# MCU.net
KiCad netlist of a schematic drawn in Altium Designer
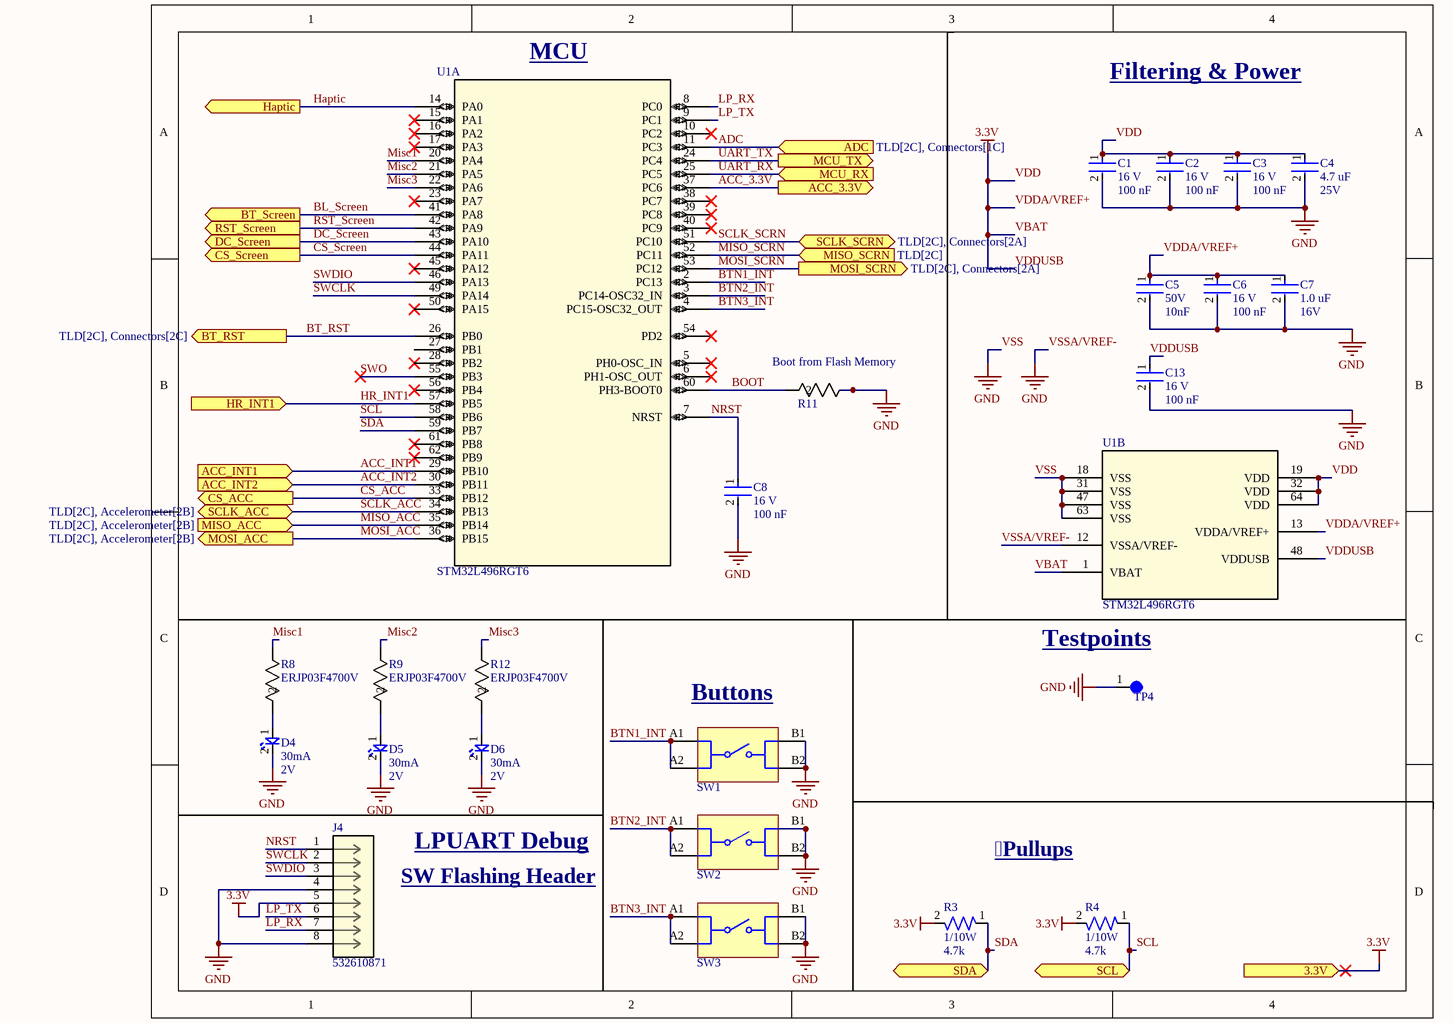
[diagram p0: MCU.SchDoc]

(export (version "E")
  (design (tool "Eeschema 10.0.6"))
  (components
    (comp (ref "C1")
      (value "CC0402KRX7R7BB104")
      (footprint "CAP-0402")
      (description "CAP CER 0.1UF 16V X7R 0402")
      (fields (field (name "VOLTAGE RATING") "16 V") (field (name "CAPACITANCE") "100 nF"))
      (libsource (lib "JLC_25") (part "CAP-0.1U-0001"))
    )
    (comp (ref "C2")
      (value "CC0402KRX7R7BB104")
      (footprint "CAP-0402")
      (description "CAP CER 0.1UF 16V X7R 0402")
      (fields (field (name "VOLTAGE RATING") "16 V") (field (name "CAPACITANCE") "100 nF"))
      (libsource (lib "JLC_25") (part "CAP-0.1U-0001"))
    )
    (comp (ref "C3")
      (value "CC0402KRX7R7BB104")
      (footprint "CAP-0402")
      (description "CAP CER 0.1UF 16V X7R 0402")
      (fields (field (name "VOLTAGE RATING") "16 V") (field (name "CAPACITANCE") "100 nF"))
      (libsource (lib "JLC_25") (part "CAP-0.1U-0001"))
    )
    (comp (ref "C4")
      (value "CC0603KRX5R8BB475")
      (footprint "CAP-0603")
      (description "CAP CER 4.7UF 25V X5R 0603")
      (fields (field (name "CAPACITANCE") "4.7 uF") (field (name "VOLTAGE") "25V"))
      (libsource (lib "JLC_25") (part "CAP-4.7U-0001"))
    )
    (comp (ref "C5")
      (value "GRM2195C1H103JA01D")
      (footprint "CAP-0805")
      (description "CAP CER 10000PF 50V C0G/NP0 0805")
      (fields (field (name "VOLTAGE") "50V") (field (name "CAPACITANCE") "10nF"))
      (libsource (lib "JLC_25") (part "CAP-10N-0001"))
    )
    (comp (ref "C6")
      (value "CC0402KRX7R7BB104")
      (footprint "CAP-0402")
      (description "CAP CER 0.1UF 16V X7R 0402")
      (fields (field (name "VOLTAGE RATING") "16 V") (field (name "CAPACITANCE") "100 nF"))
      (libsource (lib "JLC_25") (part "CAP-0.1U-0001"))
    )
    (comp (ref "C7")
      (value "CC0603KRX7R7BB105")
      (footprint "CAP-0603")
      (description "CAP CER 1UF 16V X7R 0603")
      (fields (field (name "CAPACITANCE") "1.0 uF") (field (name "VOLTAGE") "16V"))
      (libsource (lib "JLC_25") (part "CAP-1U-0002"))
    )
    (comp (ref "C8")
      (value "CC0402KRX7R7BB104")
      (footprint "CAP-0402")
      (description "CAP CER 0.1UF 16V X7R 0402")
      (fields (field (name "VOLTAGE RATING") "16 V") (field (name "CAPACITANCE") "100 nF"))
      (libsource (lib "JLC_25") (part "CAP-0.1U-0001"))
    )
    (comp (ref "C13")
      (value "CC0402KRX7R7BB104")
      (footprint "CAP-0402")
      (description "CAP CER 0.1UF 16V X7R 0402")
      (fields (field (name "VOLTAGE RATING") "16 V") (field (name "CAPACITANCE") "100 nF"))
      (libsource (lib "JLC_25") (part "CAP-0.1U-0001"))
    )
    (comp (ref "D4")
      (value "BL-HKC36G-AV-TRB")
      (footprint "LED-0603")
      (description "LED YELLOW CLEAR 0603 SMD")
      (fields (field (name "FORWARD CURRENT") "30mA") (field (name "FORWARD VOLTAGE") "2V"))
      (libsource (lib "JLC_25") (part "LED-0001"))
    )
    (comp (ref "D5")
      (value "BL-HKC36G-AV-TRB")
      (footprint "LED-0603")
      (description "LED YELLOW CLEAR 0603 SMD")
      (fields (field (name "FORWARD CURRENT") "30mA") (field (name "FORWARD VOLTAGE") "2V"))
      (libsource (lib "JLC_25") (part "LED-0001"))
    )
    (comp (ref "D6")
      (value "BL-HKC36G-AV-TRB")
      (footprint "LED-0603")
      (description "LED YELLOW CLEAR 0603 SMD")
      (fields (field (name "FORWARD CURRENT") "30mA") (field (name "FORWARD VOLTAGE") "2V"))
      (libsource (lib "JLC_25") (part "LED-0001"))
    )
    (comp (ref "J4")
      (value "532610871")
      (footprint "CONN_532610001-SD_08_MOL")
      (description "No Description Available")
      (libsource (lib "eecs373Lib") (part "Header-PICO-8"))
    )
    (comp (ref "R3")
      (value "RC0603FR-074K7L")
      (footprint "RES-0603")
      (description "RES 4.7K OHM 1% 1/10W 0603")
      (fields
        (field (name "TOLERANCE") "1%")
        (field (name "POWER") "1/10W")
        (field (name "RESISTANCE") "4.7k")
      )
      (libsource (lib "JLC_25") (part "RES-4.7k-0001"))
    )
    (comp (ref "R4")
      (value "RC0603FR-074K7L")
      (footprint "RES-0603")
      (description "RES 4.7K OHM 1% 1/10W 0603")
      (fields
        (field (name "TOLERANCE") "1%")
        (field (name "POWER") "1/10W")
        (field (name "RESISTANCE") "4.7k")
      )
      (libsource (lib "JLC_25") (part "RES-4.7k-0001"))
    )
    (comp (ref "R8")
      (value "ERJP03F4700V")
      (footprint "RES_ERJP03_PAN")
      (libsource (lib "eecs373Lib") (part "RES-470-0603"))
    )
    (comp (ref "R9")
      (value "ERJP03F4700V")
      (footprint "RES_ERJP03_PAN")
      (libsource (lib "eecs373Lib") (part "RES-470-0603"))
    )
    (comp (ref "R11")
      (value "CRCW12100000Z0EA")
      (footprint "RES_CRCW_1210_VIS")
      (description "No Description Available")
      (libsource (lib "eecs373Lib") (part "RES-0-1"))
    )
    (comp (ref "R12")
      (value "ERJP03F4700V")
      (footprint "RES_ERJP03_PAN")
      (libsource (lib "eecs373Lib") (part "RES-470-0603"))
    )
    (comp (ref "SW1")
      (value "434351045816")
      (footprint "434351045816")
      (description "WS-TASU SMT Tact Switch 4.7x3.5mm side push, SPST-NO, 12VDC, 50mA, 160g")
      (fields (field (name "MANUFACTURER") "Wurth Elektronik"))
      (libsource (lib "eecs373Lib") (part "Button-NO-90_1"))
    )
    (comp (ref "SW2")
      (value "434351045816")
      (footprint "434351045816")
      (description "WS-TASU SMT Tact Switch 4.7x3.5mm side push, SPST-NO, 12VDC, 50mA, 160g")
      (fields (field (name "MANUFACTURER") "Wurth Elektronik"))
      (libsource (lib "eecs373Lib") (part "Button-NO-90_1"))
    )
    (comp (ref "SW3")
      (value "434351045816")
      (footprint "434351045816")
      (description "WS-TASU SMT Tact Switch 4.7x3.5mm side push, SPST-NO, 12VDC, 50mA, 160g")
      (fields (field (name "MANUFACTURER") "Wurth Elektronik"))
      (libsource (lib "eecs373Lib") (part "Button-NO-90_1"))
    )
    (comp (ref "TP4")
      (value "5003")
      (footprint "TEST-POINT-0001")
      (description "Oranange PC Test Point, Miniature Phoisphor Bronze Silver Plating Through Hole Mounting Type")
      (libsource (lib "JLC_25") (part "TEST-POINT-0001"))
    )
    (comp (ref "U1")
      (value "STM32L496RGT6")
      (footprint "LQFP64-10x10mm_STM")
      (libsource (lib "eecs373Lib") (part "STM32L496RGT6"))
    )
  )
  (nets
    (net (code "1") (name "/ACC_3.3V") (class "Default")
      (node (ref "U1") (pin "37") (pinfunction "PC6_37") (pintype "bidirectional"))
    )
    (net (code "2") (name "/ACC_INT1") (class "Default")
      (node (ref "U1") (pin "29") (pinfunction "PB10_29") (pintype "bidirectional"))
    )
    (net (code "3") (name "/ACC_INT2") (class "Default")
      (node (ref "U1") (pin "30") (pinfunction "PB11_30") (pintype "bidirectional"))
    )
    (net (code "4") (name "/ADC") (class "Default")
      (node (ref "U1") (pin "11") (pinfunction "PC3_11") (pintype "bidirectional"))
    )
    (net (code "5") (name "/BL_Screen") (class "Default")
      (node (ref "U1") (pin "41") (pinfunction "PA8_41") (pintype "bidirectional"))
    )
    (net (code "6") (name "/BOOT") (class "Default")
      (node (ref "R11") (pin "2") (pinfunction "2_2") (pintype "passive"))
      (node (ref "U1") (pin "60") (pinfunction "PH3-BOOT0_60") (pintype "bidirectional"))
    )
    (net (code "7") (name "/BTN1_INT") (class "Default")
      (node (ref "SW1") (pin "A1") (pinfunction "A1_A1") (pintype "passive"))
      (node (ref "SW1") (pin "A2") (pinfunction "A2_A2") (pintype "passive"))
      (node (ref "U1") (pin "2") (pinfunction "PC13_2") (pintype "bidirectional"))
    )
    (net (code "8") (name "/BTN2_INT") (class "Default")
      (node (ref "SW2") (pin "A1") (pinfunction "A1_A1") (pintype "passive"))
      (node (ref "SW2") (pin "A2") (pinfunction "A2_A2") (pintype "passive"))
      (node (ref "U1") (pin "3") (pinfunction "PC14-OSC32_IN_3") (pintype "bidirectional"))
    )
    (net (code "9") (name "/BTN3_INT") (class "Default")
      (node (ref "SW3") (pin "A1") (pinfunction "A1_A1") (pintype "passive"))
      (node (ref "SW3") (pin "A2") (pinfunction "A2_A2") (pintype "passive"))
      (node (ref "U1") (pin "4") (pinfunction "PC15-OSC32_OUT_4") (pintype "bidirectional"))
    )
    (net (code "10") (name "/BT_RST") (class "Default")
      (node (ref "U1") (pin "26") (pinfunction "PB0_26") (pintype "bidirectional"))
    )
    (net (code "11") (name "/CS_ACC") (class "Default")
      (node (ref "U1") (pin "33") (pinfunction "PB12_33") (pintype "bidirectional"))
    )
    (net (code "12") (name "/CS_Screen") (class "Default")
      (node (ref "U1") (pin "44") (pinfunction "PA11_44") (pintype "bidirectional"))
    )
    (net (code "13") (name "/DC_Screen") (class "Default")
      (node (ref "U1") (pin "43") (pinfunction "PA10_43") (pintype "bidirectional"))
    )
    (net (code "14") (name "/HR_INT1") (class "Default")
      (node (ref "U1") (pin "57") (pinfunction "PB5_57") (pintype "bidirectional"))
    )
    (net (code "15") (name "/Haptic") (class "Default")
      (node (ref "U1") (pin "14") (pinfunction "PA0_14") (pintype "bidirectional"))
    )
    (net (code "16") (name "/LP_RX") (class "Default")
      (node (ref "J4") (pin "7") (pinfunction "7_7") (pintype "passive"))
      (node (ref "U1") (pin "8") (pinfunction "PC0_8") (pintype "bidirectional"))
    )
    (net (code "17") (name "/LP_TX") (class "Default")
      (node (ref "J4") (pin "6") (pinfunction "6_6") (pintype "passive"))
      (node (ref "U1") (pin "9") (pinfunction "PC1_9") (pintype "bidirectional"))
    )
    (net (code "18") (name "/MISO_ACC") (class "Default")
      (node (ref "U1") (pin "35") (pinfunction "PB14_35") (pintype "bidirectional"))
    )
    (net (code "19") (name "/MISO_SCRN") (class "Default")
      (node (ref "U1") (pin "52") (pinfunction "PC11_52") (pintype "bidirectional"))
    )
    (net (code "20") (name "/MOSI_ACC") (class "Default")
      (node (ref "U1") (pin "36") (pinfunction "PB15_36") (pintype "bidirectional"))
    )
    (net (code "21") (name "/MOSI_SCRN") (class "Default")
      (node (ref "U1") (pin "53") (pinfunction "PC12_53") (pintype "bidirectional"))
    )
    (net (code "22") (name "/Misc1") (class "Default")
      (node (ref "R8") (pin "1") (pinfunction "1_1") (pintype "passive"))
      (node (ref "U1") (pin "20") (pinfunction "PA4_20") (pintype "bidirectional"))
    )
    (net (code "23") (name "/Misc2") (class "Default")
      (node (ref "R9") (pin "1") (pinfunction "1_1") (pintype "passive"))
      (node (ref "U1") (pin "21") (pinfunction "PA5_21") (pintype "bidirectional"))
    )
    (net (code "24") (name "/Misc3") (class "Default")
      (node (ref "R12") (pin "1") (pinfunction "1_1") (pintype "passive"))
      (node (ref "U1") (pin "22") (pinfunction "PA6_22") (pintype "bidirectional"))
    )
    (net (code "25") (name "/NRST") (class "Default")
      (node (ref "C8") (pin "1") (pinfunction "1_1") (pintype "passive"))
      (node (ref "J4") (pin "1") (pinfunction "1_1") (pintype "passive"))
      (node (ref "U1") (pin "7") (pinfunction "NRST_7") (pintype "bidirectional"))
    )
    (net (code "26") (name "/RST_Screen") (class "Default")
      (node (ref "U1") (pin "42") (pinfunction "PA9_42") (pintype "bidirectional"))
    )
    (net (code "27") (name "/SCL") (class "Default")
      (node (ref "R4") (pin "1") (pinfunction "1_1") (pintype "passive"))
      (node (ref "U1") (pin "58") (pinfunction "PB6_58") (pintype "bidirectional"))
    )
    (net (code "28") (name "/SCLK_ACC") (class "Default")
      (node (ref "U1") (pin "34") (pinfunction "PB13_34") (pintype "bidirectional"))
    )
    (net (code "29") (name "/SCLK_SCRN") (class "Default")
      (node (ref "U1") (pin "51") (pinfunction "PC10_51") (pintype "bidirectional"))
    )
    (net (code "30") (name "/SDA") (class "Default")
      (node (ref "R3") (pin "1") (pinfunction "1_1") (pintype "passive"))
      (node (ref "U1") (pin "59") (pinfunction "PB7_59") (pintype "bidirectional"))
    )
    (net (code "31") (name "/SWCLK") (class "Default")
      (node (ref "J4") (pin "2") (pinfunction "2_2") (pintype "passive"))
      (node (ref "U1") (pin "49") (pinfunction "PA14_49") (pintype "bidirectional"))
    )
    (net (code "32") (name "/SWDIO") (class "Default")
      (node (ref "J4") (pin "3") (pinfunction "3_3") (pintype "passive"))
      (node (ref "U1") (pin "46") (pinfunction "PA13_46") (pintype "bidirectional"))
    )
    (net (code "33") (name "/SWO") (class "Default")
      (node (ref "U1") (pin "55") (pinfunction "PB3_55") (pintype "bidirectional+no_connect"))
    )
    (net (code "34") (name "/UART_RX") (class "Default")
      (node (ref "U1") (pin "25") (pinfunction "PC5_25") (pintype "bidirectional"))
    )
    (net (code "35") (name "/UART_TX") (class "Default")
      (node (ref "U1") (pin "24") (pinfunction "PC4_24") (pintype "bidirectional"))
    )
    (net (code "36") (name "3.3V") (class "Default")
      (node (ref "C1") (pin "1") (pinfunction "1_1") (pintype "passive"))
      (node (ref "C13") (pin "1") (pinfunction "1_1") (pintype "passive"))
      (node (ref "C2") (pin "1") (pinfunction "1_1") (pintype "passive"))
      (node (ref "C3") (pin "1") (pinfunction "1_1") (pintype "passive"))
      (node (ref "C4") (pin "1") (pinfunction "1_1") (pintype "passive"))
      (node (ref "C5") (pin "1") (pinfunction "1_1") (pintype "passive"))
      (node (ref "C6") (pin "1") (pinfunction "1_1") (pintype "passive"))
      (node (ref "C7") (pin "1") (pinfunction "1_1") (pintype "passive"))
      (node (ref "J4") (pin "5") (pinfunction "5_5") (pintype "passive"))
      (node (ref "R3") (pin "2") (pinfunction "2_2") (pintype "passive"))
      (node (ref "R4") (pin "2") (pinfunction "2_2") (pintype "passive"))
      (node (ref "U1") (pin "1") (pinfunction "VBAT_1") (pintype "power_in"))
      (node (ref "U1") (pin "13") (pinfunction "VDDA/VREF+_13") (pintype "power_in"))
      (node (ref "U1") (pin "19") (pinfunction "VDD_19") (pintype "power_in"))
      (node (ref "U1") (pin "32") (pinfunction "VDD_32") (pintype "power_in"))
      (node (ref "U1") (pin "48") (pinfunction "VDDUSB_48") (pintype "power_in"))
      (node (ref "U1") (pin "64") (pinfunction "VDD_64") (pintype "power_in"))
    )
    (net (code "37") (name "GND") (class "Default")
      (node (ref "C1") (pin "2") (pinfunction "2_2") (pintype "passive"))
      (node (ref "C13") (pin "2") (pinfunction "2_2") (pintype "passive"))
      (node (ref "C2") (pin "2") (pinfunction "2_2") (pintype "passive"))
      (node (ref "C3") (pin "2") (pinfunction "2_2") (pintype "passive"))
      (node (ref "C4") (pin "2") (pinfunction "2_2") (pintype "passive"))
      (node (ref "C5") (pin "2") (pinfunction "2_2") (pintype "passive"))
      (node (ref "C6") (pin "2") (pinfunction "2_2") (pintype "passive"))
      (node (ref "C7") (pin "2") (pinfunction "2_2") (pintype "passive"))
      (node (ref "C8") (pin "2") (pinfunction "2_2") (pintype "passive"))
      (node (ref "D4") (pin "2") (pinfunction "2_2") (pintype "passive"))
      (node (ref "D5") (pin "2") (pinfunction "2_2") (pintype "passive"))
      (node (ref "D6") (pin "2") (pinfunction "2_2") (pintype "passive"))
      (node (ref "J4") (pin "4") (pinfunction "4_4") (pintype "passive"))
      (node (ref "J4") (pin "8") (pinfunction "8_8") (pintype "passive"))
      (node (ref "R11") (pin "1") (pinfunction "1_1") (pintype "passive"))
      (node (ref "SW1") (pin "B1") (pinfunction "B1_B1") (pintype "passive"))
      (node (ref "SW1") (pin "B2") (pinfunction "B2_B2") (pintype "passive"))
      (node (ref "SW2") (pin "B1") (pinfunction "B1_B1") (pintype "passive"))
      (node (ref "SW2") (pin "B2") (pinfunction "B2_B2") (pintype "passive"))
      (node (ref "SW3") (pin "B1") (pinfunction "B1_B1") (pintype "passive"))
      (node (ref "SW3") (pin "B2") (pinfunction "B2_B2") (pintype "passive"))
      (node (ref "TP4") (pin "1") (pinfunction "0_1") (pintype "passive"))
      (node (ref "U1") (pin "12") (pinfunction "VSSA/VREF-_12") (pintype "power_in"))
      (node (ref "U1") (pin "18") (pinfunction "VSS_18") (pintype "power_in"))
      (node (ref "U1") (pin "31") (pinfunction "VSS_31") (pintype "power_in"))
      (node (ref "U1") (pin "47") (pinfunction "VSS_47") (pintype "power_in"))
      (node (ref "U1") (pin "63") (pinfunction "VSS_63") (pintype "power_in"))
    )
    (net (code "38") (name "Net-(D4-Pad1)") (class "Default")
      (node (ref "D4") (pin "1") (pinfunction "1_1") (pintype "passive"))
      (node (ref "R8") (pin "2") (pinfunction "2_2") (pintype "passive"))
    )
    (net (code "39") (name "Net-(D5-Pad1)") (class "Default")
      (node (ref "D5") (pin "1") (pinfunction "1_1") (pintype "passive"))
      (node (ref "R9") (pin "2") (pinfunction "2_2") (pintype "passive"))
    )
    (net (code "40") (name "Net-(D6-Pad1)") (class "Default")
      (node (ref "D6") (pin "1") (pinfunction "1_1") (pintype "passive"))
      (node (ref "R12") (pin "2") (pinfunction "2_2") (pintype "passive"))
    )
    (net (code "41") (name "unconnected-(U1A-PA1-Pad15)") (class "Default")
      (node (ref "U1") (pin "15") (pinfunction "PA1_15") (pintype "bidirectional+no_connect"))
    )
    (net (code "42") (name "unconnected-(U1A-PA2-Pad16)") (class "Default")
      (node (ref "U1") (pin "16") (pinfunction "PA2_16") (pintype "bidirectional+no_connect"))
    )
    (net (code "43") (name "unconnected-(U1A-PA3-Pad17)") (class "Default")
      (node (ref "U1") (pin "17") (pinfunction "PA3_17") (pintype "bidirectional+no_connect"))
    )
    (net (code "44") (name "unconnected-(U1A-PA7-Pad23)") (class "Default")
      (node (ref "U1") (pin "23") (pinfunction "PA7_23") (pintype "bidirectional+no_connect"))
    )
    (net (code "45") (name "unconnected-(U1A-PA12-Pad45)") (class "Default")
      (node (ref "U1") (pin "45") (pinfunction "PA12_45") (pintype "bidirectional+no_connect"))
    )
    (net (code "46") (name "unconnected-(U1A-PA15-Pad50)") (class "Default")
      (node (ref "U1") (pin "50") (pinfunction "PA15_50") (pintype "bidirectional+no_connect"))
    )
    (net (code "47") (name "unconnected-(U1A-PB1-Pad27)") (class "Default")
      (node (ref "U1") (pin "27") (pinfunction "PB1_27") (pintype "bidirectional"))
    )
    (net (code "48") (name "unconnected-(U1A-PB2-Pad28)") (class "Default")
      (node (ref "U1") (pin "28") (pinfunction "PB2_28") (pintype "bidirectional+no_connect"))
    )
    (net (code "49") (name "unconnected-(U1A-PB4-Pad56)") (class "Default")
      (node (ref "U1") (pin "56") (pinfunction "PB4_56") (pintype "bidirectional+no_connect"))
    )
    (net (code "50") (name "unconnected-(U1A-PB8-Pad61)") (class "Default")
      (node (ref "U1") (pin "61") (pinfunction "PB8_61") (pintype "bidirectional+no_connect"))
    )
    (net (code "51") (name "unconnected-(U1A-PB9-Pad62)") (class "Default")
      (node (ref "U1") (pin "62") (pinfunction "PB9_62") (pintype "bidirectional+no_connect"))
    )
    (net (code "52") (name "unconnected-(U1A-PC2-Pad10)") (class "Default")
      (node (ref "U1") (pin "10") (pinfunction "PC2_10") (pintype "bidirectional+no_connect"))
    )
    (net (code "53") (name "unconnected-(U1A-PC7-Pad38)") (class "Default")
      (node (ref "U1") (pin "38") (pinfunction "PC7_38") (pintype "bidirectional+no_connect"))
    )
    (net (code "54") (name "unconnected-(U1A-PC8-Pad39)") (class "Default")
      (node (ref "U1") (pin "39") (pinfunction "PC8_39") (pintype "bidirectional+no_connect"))
    )
    (net (code "55") (name "unconnected-(U1A-PC9-Pad40)") (class "Default")
      (node (ref "U1") (pin "40") (pinfunction "PC9_40") (pintype "bidirectional+no_connect"))
    )
    (net (code "56") (name "unconnected-(U1A-PD2-Pad54)") (class "Default")
      (node (ref "U1") (pin "54") (pinfunction "PD2_54") (pintype "bidirectional+no_connect"))
    )
    (net (code "57") (name "unconnected-(U1A-PH0-OSC_IN-Pad5)") (class "Default")
      (node (ref "U1") (pin "5") (pinfunction "PH0-OSC_IN_5") (pintype "bidirectional+no_connect"))
    )
    (net (code "58") (name "unconnected-(U1A-PH1-OSC_OUT-Pad6)") (class "Default")
      (node (ref "U1") (pin "6") (pinfunction "PH1-OSC_OUT_6") (pintype "bidirectional+no_connect"))
    )
  )
)
